# PS004.net
KiCad netlist of a schematic drawn in Altium Designer
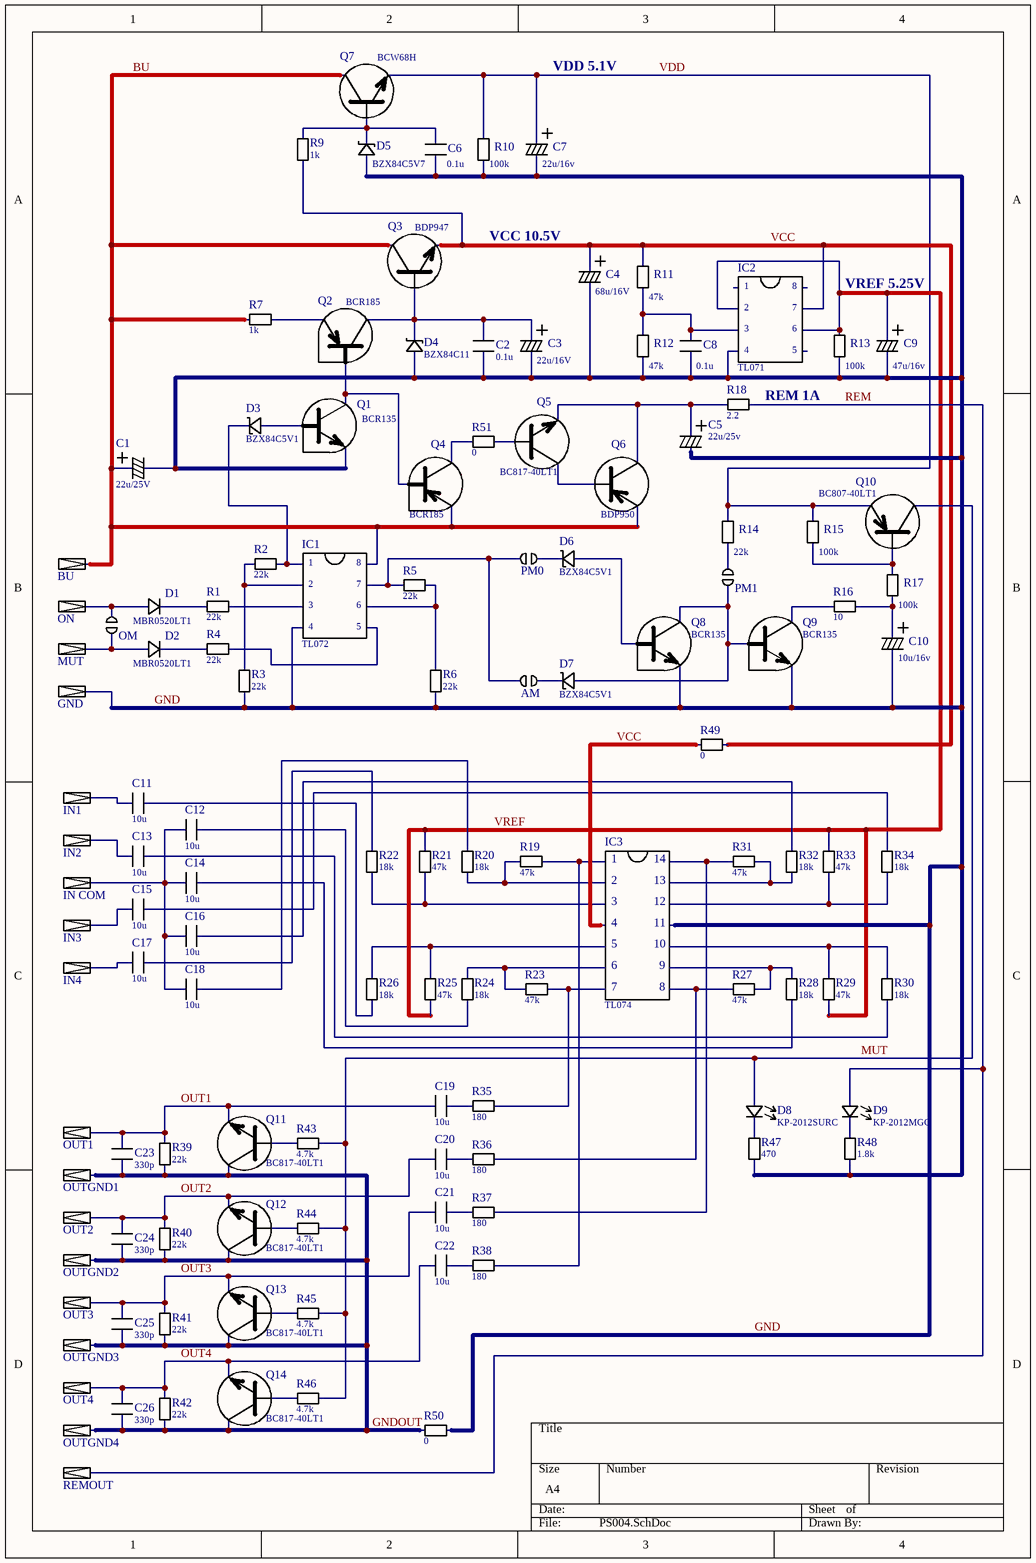
[diagram p0: PS004.SchDoc]

(export (version "E")
  (design (tool "Eeschema 10.0.6"))
  (components
    (comp (ref "AM") (value "SC plan") (footprint "SC") (libsource (lib "PS004") (part "SC plan")))
    (comp (ref "BU") (value "IN plan") (footprint "IO") (libsource (lib "PS004") (part "IN plan")))
    (comp (ref "C1")
      (value "C plan pol")
      (footprint "C")
      (fields (field (name "CAPASITANCE") "22u/25V"))
      (libsource (lib "PS004") (part "C plan pol"))
    )
    (comp (ref "C2")
      (value "C plan cer")
      (footprint "0805")
      (fields (field (name "CAPASITANCE") "0.1u"))
      (libsource (lib "PS004") (part "C plan cer"))
    )
    (comp (ref "C3")
      (value "C plan pol")
      (footprint "C")
      (fields (field (name "CAPASITANCE") "22u/16V"))
      (libsource (lib "PS004") (part "C plan pol"))
    )
    (comp (ref "C4")
      (value "C plan pol")
      (footprint "C")
      (fields (field (name "CAPASITANCE") "68u/16V"))
      (libsource (lib "PS004") (part "C plan pol"))
    )
    (comp (ref "C5")
      (value "C plan pol")
      (footprint "C")
      (fields (field (name "CAPASITANCE") "22u/25v"))
      (libsource (lib "PS004") (part "C plan pol"))
    )
    (comp (ref "C6")
      (value "C plan cer")
      (footprint "0805")
      (fields (field (name "CAPASITANCE") "0.1u"))
      (libsource (lib "PS004") (part "C plan cer"))
    )
    (comp (ref "C7")
      (value "C plan pol")
      (footprint "C")
      (fields (field (name "CAPASITANCE") "22u/16v"))
      (libsource (lib "PS004") (part "C plan pol"))
    )
    (comp (ref "C8")
      (value "C plan cer")
      (footprint "0805")
      (fields (field (name "CAPASITANCE") "0.1u"))
      (libsource (lib "PS004") (part "C plan cer"))
    )
    (comp (ref "C9")
      (value "C plan pol")
      (footprint "C")
      (fields (field (name "CAPASITANCE") "47u/16v"))
      (libsource (lib "PS004") (part "C plan pol"))
    )
    (comp (ref "C10")
      (value "C plan pol")
      (footprint "C")
      (fields (field (name "CAPASITANCE") "10u/16v"))
      (libsource (lib "PS004") (part "C plan pol"))
    )
    (comp (ref "C11")
      (value "C plan cer")
      (footprint "1206")
      (fields (field (name "CAPASITANCE") "10u"))
      (libsource (lib "PS004") (part "C plan cer"))
    )
    (comp (ref "C12")
      (value "C plan cer")
      (footprint "1206")
      (fields (field (name "CAPASITANCE") "10u"))
      (libsource (lib "PS004") (part "C plan cer"))
    )
    (comp (ref "C13")
      (value "C plan cer")
      (footprint "1206")
      (fields (field (name "CAPASITANCE") "10u"))
      (libsource (lib "PS004") (part "C plan cer"))
    )
    (comp (ref "C14")
      (value "C plan cer")
      (footprint "1206")
      (fields (field (name "CAPASITANCE") "10u"))
      (libsource (lib "PS004") (part "C plan cer"))
    )
    (comp (ref "C15")
      (value "C plan cer")
      (footprint "1206")
      (fields (field (name "CAPASITANCE") "10u"))
      (libsource (lib "PS004") (part "C plan cer"))
    )
    (comp (ref "C16")
      (value "C plan cer")
      (footprint "1206")
      (fields (field (name "CAPASITANCE") "10u"))
      (libsource (lib "PS004") (part "C plan cer"))
    )
    (comp (ref "C17")
      (value "C plan cer")
      (footprint "1206")
      (fields (field (name "CAPASITANCE") "10u"))
      (libsource (lib "PS004") (part "C plan cer"))
    )
    (comp (ref "C18")
      (value "C plan cer")
      (footprint "1206")
      (fields (field (name "CAPASITANCE") "10u"))
      (libsource (lib "PS004") (part "C plan cer"))
    )
    (comp (ref "C19")
      (value "C plan cer")
      (footprint "1206")
      (fields (field (name "CAPASITANCE") "10u"))
      (libsource (lib "PS004") (part "C plan cer"))
    )
    (comp (ref "C20")
      (value "C plan cer")
      (footprint "1206")
      (fields (field (name "CAPASITANCE") "10u"))
      (libsource (lib "PS004") (part "C plan cer"))
    )
    (comp (ref "C21")
      (value "C plan cer")
      (footprint "1206")
      (fields (field (name "CAPASITANCE") "10u"))
      (libsource (lib "PS004") (part "C plan cer"))
    )
    (comp (ref "C22")
      (value "C plan cer")
      (footprint "1206")
      (fields (field (name "CAPASITANCE") "10u"))
      (libsource (lib "PS004") (part "C plan cer"))
    )
    (comp (ref "C23")
      (value "C plan cer")
      (footprint "0805")
      (fields (field (name "CAPASITANCE") "330p"))
      (libsource (lib "PS004") (part "C plan cer"))
    )
    (comp (ref "C24")
      (value "C plan cer")
      (footprint "0805")
      (fields (field (name "CAPASITANCE") "330p"))
      (libsource (lib "PS004") (part "C plan cer"))
    )
    (comp (ref "C25")
      (value "C plan cer")
      (footprint "0805")
      (fields (field (name "CAPASITANCE") "330p"))
      (libsource (lib "PS004") (part "C plan cer"))
    )
    (comp (ref "C26")
      (value "C plan cer")
      (footprint "0805")
      (fields (field (name "CAPASITANCE") "330p"))
      (libsource (lib "PS004") (part "C plan cer"))
    )
    (comp (ref "D1")
      (value "D plan")
      (footprint "SOD-123")
      (fields (field (name "NAME") "MBR0520LT1"))
      (libsource (lib "PS004") (part "D plan"))
    )
    (comp (ref "D2")
      (value "D plan")
      (footprint "SOD-123")
      (fields (field (name "NAME") "MBR0520LT1"))
      (libsource (lib "PS004") (part "D plan"))
    )
    (comp (ref "D3")
      (value "DZ plan")
      (footprint "SOT-23")
      (fields (field (name "NAME") "BZX84C5V1"))
      (libsource (lib "PS004") (part "DZ plan"))
    )
    (comp (ref "D4")
      (value "DZ plan")
      (footprint "SOT-23")
      (fields (field (name "NAME") "BZX84C11"))
      (libsource (lib "PS004") (part "DZ plan"))
    )
    (comp (ref "D5")
      (value "DZ plan")
      (footprint "SOT-23")
      (fields (field (name "NAME") "BZX84C5V7"))
      (libsource (lib "PS004") (part "DZ plan"))
    )
    (comp (ref "D6")
      (value "DZ plan")
      (footprint "SOT-23")
      (fields (field (name "NAME") "BZX84C5V1"))
      (libsource (lib "PS004") (part "DZ plan"))
    )
    (comp (ref "D7")
      (value "DZ plan")
      (footprint "SOT-23")
      (fields (field (name "NAME") "BZX84C5V1"))
      (libsource (lib "PS004") (part "DZ plan"))
    )
    (comp (ref "D8")
      (value "DI plan")
      (footprint "0805 DI")
      (fields (field (name "NAME") "KP-2012SURC"))
      (libsource (lib "PS004") (part "DI plan"))
    )
    (comp (ref "D9")
      (value "DI plan")
      (footprint "0805 DI")
      (fields (field (name "NAME") "KP-2012MGC"))
      (libsource (lib "PS004") (part "DI plan"))
    )
    (comp (ref "GND") (value "IN plan") (footprint "IO") (libsource (lib "PS004") (part "IN plan")))
    (comp (ref "IC1")
      (value "IC 8 plan")
      (footprint "SO-8")
      (fields (field (name "NAME") "TL072"))
      (libsource (lib "PS004") (part "IC 8 plan"))
    )
    (comp (ref "IC2")
      (value "IC 8 plan")
      (footprint "SO-8")
      (fields (field (name "NAME") "TL071"))
      (libsource (lib "PS004") (part "IC 8 plan"))
    )
    (comp (ref "IC3")
      (value "IC 14 plan")
      (footprint "SO-14")
      (fields (field (name "NAME") "TL074"))
      (libsource (lib "PS004") (part "IC 14 plan"))
    )
    (comp (ref "IN COM") (value "IN plan") (footprint "IO") (libsource (lib "PS004") (part "IN plan")))
    (comp (ref "IN1") (value "IN plan") (footprint "IO") (libsource (lib "PS004") (part "IN plan")))
    (comp (ref "IN2") (value "IN plan") (footprint "IO") (libsource (lib "PS004") (part "IN plan")))
    (comp (ref "IN3") (value "IN plan") (footprint "IO") (libsource (lib "PS004") (part "IN plan")))
    (comp (ref "IN4") (value "IN plan") (footprint "IO") (libsource (lib "PS004") (part "IN plan")))
    (comp (ref "MUT") (value "IN plan") (footprint "IO") (libsource (lib "PS004") (part "IN plan")))
    (comp (ref "OM") (value "SC plan") (footprint "SC") (libsource (lib "") (part "SC plan_1")))
    (comp (ref "ON") (value "IN plan") (footprint "IO") (libsource (lib "PS004") (part "IN plan")))
    (comp (ref "OUT1") (value "OUT plan") (footprint "IO") (libsource (lib "PS004") (part "OUT plan")))
    (comp (ref "OUT2") (value "OUT plan") (footprint "IO") (libsource (lib "PS004") (part "OUT plan")))
    (comp (ref "OUT3") (value "OUT plan") (footprint "IO") (libsource (lib "PS004") (part "OUT plan")))
    (comp (ref "OUT4") (value "OUT plan") (footprint "IO") (libsource (lib "PS004") (part "OUT plan")))
    (comp (ref "OUTGND1") (value "OUT plan") (footprint "IO") (libsource (lib "PS004") (part "OUT plan")))
    (comp (ref "OUTGND2") (value "OUT plan") (footprint "IO") (libsource (lib "PS004") (part "OUT plan")))
    (comp (ref "OUTGND3") (value "OUT plan") (footprint "IO") (libsource (lib "PS004") (part "OUT plan")))
    (comp (ref "OUTGND4") (value "OUT plan") (footprint "IO") (libsource (lib "PS004") (part "OUT plan")))
    (comp (ref "PM0") (value "SC plan") (footprint "SC") (libsource (lib "PS004") (part "SC plan")))
    (comp (ref "PM1") (value "SC plan") (footprint "SC") (libsource (lib "") (part "SC plan_1")))
    (comp (ref "Q1")
      (value "QD npn plan")
      (footprint "SOT-23")
      (fields (field (name "NAME") "BCR135"))
      (libsource (lib "PS004") (part "QD npn plan"))
    )
    (comp (ref "Q2")
      (value "QD pnp plan")
      (footprint "SOT-23")
      (fields (field (name "NAME") "BCR185"))
      (libsource (lib "PS004") (part "QD pnp plan"))
    )
    (comp (ref "Q3")
      (value "Q npn plan")
      (footprint "SOT-223")
      (fields (field (name "NAME") "BDP947"))
      (libsource (lib "") (part "Q npn plan_2"))
    )
    (comp (ref "Q4")
      (value "QD pnp plan")
      (footprint "SOT-23")
      (fields (field (name "NAME") "BCR185"))
      (libsource (lib "") (part "QD pnp plan_1"))
    )
    (comp (ref "Q5")
      (value "Q npn plan")
      (footprint "SOT-23")
      (fields (field (name "NAME") "BC817-40LT1"))
      (libsource (lib "") (part "Q npn plan_1"))
    )
    (comp (ref "Q6")
      (value "Q pnp plan")
      (footprint "SOT-223")
      (fields (field (name "NAME") "BDP950"))
      (libsource (lib "") (part "Q pnp plan_1"))
    )
    (comp (ref "Q7")
      (value "Q npn plan")
      (footprint "SOT-23")
      (fields (field (name "NAME") "BCW68H"))
      (libsource (lib "") (part "Q npn plan_2"))
    )
    (comp (ref "Q8")
      (value "QD npn plan")
      (footprint "SOT-23")
      (fields (field (name "NAME") "BCR135"))
      (libsource (lib "PS004") (part "QD npn plan"))
    )
    (comp (ref "Q9")
      (value "QD npn plan")
      (footprint "SOT-23")
      (fields (field (name "NAME") "BCR135"))
      (libsource (lib "PS004") (part "QD npn plan"))
    )
    (comp (ref "Q10")
      (value "Q pnp plan")
      (footprint "SOT-23")
      (fields (field (name "NAME") "BC807-40LT1"))
      (libsource (lib "PS004") (part "Q pnp plan"))
    )
    (comp (ref "Q11")
      (value "Q npn plan")
      (footprint "SOT-23")
      (fields (field (name "NAME") "BC817-40LT1"))
      (libsource (lib "PS004") (part "Q npn plan"))
    )
    (comp (ref "Q12")
      (value "Q npn plan")
      (footprint "SOT-23")
      (fields (field (name "NAME") "BC817-40LT1"))
      (libsource (lib "PS004") (part "Q npn plan"))
    )
    (comp (ref "Q13")
      (value "Q npn plan")
      (footprint "SOT-23")
      (fields (field (name "NAME") "BC817-40LT1"))
      (libsource (lib "PS004") (part "Q npn plan"))
    )
    (comp (ref "Q14")
      (value "Q npn plan")
      (footprint "SOT-23")
      (fields (field (name "NAME") "BC817-40LT1"))
      (libsource (lib "PS004") (part "Q npn plan"))
    )
    (comp (ref "R1")
      (value "R plan")
      (footprint "0805")
      (fields (field (name "RESISTANCE") "22k"))
      (libsource (lib "PS004") (part "R plan"))
    )
    (comp (ref "R2")
      (value "R plan")
      (footprint "0805")
      (fields (field (name "RESISTANCE") "22k"))
      (libsource (lib "PS004") (part "R plan"))
    )
    (comp (ref "R3")
      (value "R plan")
      (footprint "0805")
      (fields (field (name "RESISTANCE") "22k"))
      (libsource (lib "PS004") (part "R plan"))
    )
    (comp (ref "R4")
      (value "R plan")
      (footprint "0805")
      (fields (field (name "RESISTANCE") "22k"))
      (libsource (lib "PS004") (part "R plan"))
    )
    (comp (ref "R5")
      (value "R plan")
      (footprint "0805")
      (fields (field (name "RESISTANCE") "22k"))
      (libsource (lib "PS004") (part "R plan"))
    )
    (comp (ref "R6")
      (value "R plan")
      (footprint "0805")
      (fields (field (name "RESISTANCE") "22k"))
      (libsource (lib "PS004") (part "R plan"))
    )
    (comp (ref "R7")
      (value "R plan")
      (footprint "0805")
      (fields (field (name "RESISTANCE") "1k"))
      (libsource (lib "PS004") (part "R plan"))
    )
    (comp (ref "R9")
      (value "R plan")
      (footprint "0805")
      (fields (field (name "RESISTANCE") "1k"))
      (libsource (lib "PS004") (part "R plan"))
    )
    (comp (ref "R10")
      (value "R plan")
      (footprint "0805")
      (fields (field (name "RESISTANCE") "100k"))
      (libsource (lib "PS004") (part "R plan"))
    )
    (comp (ref "R11")
      (value "R plan")
      (footprint "0805")
      (fields (field (name "RESISTANCE") "47k"))
      (libsource (lib "PS004") (part "R plan"))
    )
    (comp (ref "R12")
      (value "R plan")
      (footprint "0805")
      (fields (field (name "RESISTANCE") "47k"))
      (libsource (lib "PS004") (part "R plan"))
    )
    (comp (ref "R13")
      (value "R plan")
      (footprint "0805")
      (fields (field (name "RESISTANCE") "100k"))
      (libsource (lib "PS004") (part "R plan"))
    )
    (comp (ref "R14")
      (value "R plan")
      (footprint "0805")
      (fields (field (name "RESISTANCE") "22k"))
      (libsource (lib "PS004") (part "R plan"))
    )
    (comp (ref "R15")
      (value "R plan")
      (footprint "0805")
      (fields (field (name "RESISTANCE") "100k"))
      (libsource (lib "PS004") (part "R plan"))
    )
    (comp (ref "R16")
      (value "R plan")
      (footprint "0805")
      (fields (field (name "RESISTANCE") "10"))
      (libsource (lib "PS004") (part "R plan"))
    )
    (comp (ref "R17")
      (value "R plan")
      (footprint "0805")
      (fields (field (name "RESISTANCE") "100k"))
      (libsource (lib "PS004") (part "R plan"))
    )
    (comp (ref "R18")
      (value "R plan")
      (footprint "1210")
      (fields (field (name "RESISTANCE") "2.2"))
      (libsource (lib "PS004") (part "R plan"))
    )
    (comp (ref "R19")
      (value "R plan")
      (footprint "0805")
      (fields (field (name "RESISTANCE") "47k"))
      (libsource (lib "PS004") (part "R plan"))
    )
    (comp (ref "R20")
      (value "R plan")
      (footprint "0805")
      (fields (field (name "RESISTANCE") "18k"))
      (libsource (lib "PS004") (part "R plan"))
    )
    (comp (ref "R21")
      (value "R plan")
      (footprint "0805")
      (fields (field (name "RESISTANCE") "47k"))
      (libsource (lib "PS004") (part "R plan"))
    )
    (comp (ref "R22")
      (value "R plan")
      (footprint "0805")
      (fields (field (name "RESISTANCE") "18k"))
      (libsource (lib "PS004") (part "R plan"))
    )
    (comp (ref "R23")
      (value "R plan")
      (footprint "0805")
      (fields (field (name "RESISTANCE") "47k"))
      (libsource (lib "PS004") (part "R plan"))
    )
    (comp (ref "R24")
      (value "R plan")
      (footprint "0805")
      (fields (field (name "RESISTANCE") "18k"))
      (libsource (lib "PS004") (part "R plan"))
    )
    (comp (ref "R25")
      (value "R plan")
      (footprint "0805")
      (fields (field (name "RESISTANCE") "47k"))
      (libsource (lib "PS004") (part "R plan"))
    )
    (comp (ref "R26")
      (value "R plan")
      (footprint "0805")
      (fields (field (name "RESISTANCE") "18k"))
      (libsource (lib "PS004") (part "R plan"))
    )
    (comp (ref "R27")
      (value "R plan")
      (footprint "0805")
      (fields (field (name "RESISTANCE") "47k"))
      (libsource (lib "PS004") (part "R plan"))
    )
    (comp (ref "R28")
      (value "R plan")
      (footprint "0805")
      (fields (field (name "RESISTANCE") "18k"))
      (libsource (lib "PS004") (part "R plan"))
    )
    (comp (ref "R29")
      (value "R plan")
      (footprint "0805")
      (fields (field (name "RESISTANCE") "47k"))
      (libsource (lib "PS004") (part "R plan"))
    )
    (comp (ref "R30")
      (value "R plan")
      (footprint "0805")
      (fields (field (name "RESISTANCE") "18k"))
      (libsource (lib "PS004") (part "R plan"))
    )
    (comp (ref "R31")
      (value "R plan")
      (footprint "0805")
      (fields (field (name "RESISTANCE") "47k"))
      (libsource (lib "PS004") (part "R plan"))
    )
    (comp (ref "R32")
      (value "R plan")
      (footprint "0805")
      (fields (field (name "RESISTANCE") "18k"))
      (libsource (lib "PS004") (part "R plan"))
    )
    (comp (ref "R33")
      (value "R plan")
      (footprint "0805")
      (fields (field (name "RESISTANCE") "47k"))
      (libsource (lib "PS004") (part "R plan"))
    )
    (comp (ref "R34")
      (value "R plan")
      (footprint "0805")
      (fields (field (name "RESISTANCE") "18k"))
      (libsource (lib "PS004") (part "R plan"))
    )
    (comp (ref "R35")
      (value "R plan")
      (footprint "0805")
      (fields (field (name "RESISTANCE") "180"))
      (libsource (lib "PS004") (part "R plan"))
    )
    (comp (ref "R36")
      (value "R plan")
      (footprint "0805")
      (fields (field (name "RESISTANCE") "180"))
      (libsource (lib "PS004") (part "R plan"))
    )
    (comp (ref "R37")
      (value "R plan")
      (footprint "0805")
      (fields (field (name "RESISTANCE") "180"))
      (libsource (lib "PS004") (part "R plan"))
    )
    (comp (ref "R38")
      (value "R plan")
      (footprint "0805")
      (fields (field (name "RESISTANCE") "180"))
      (libsource (lib "PS004") (part "R plan"))
    )
    (comp (ref "R39")
      (value "R plan")
      (footprint "0805")
      (fields (field (name "RESISTANCE") "22k"))
      (libsource (lib "PS004") (part "R plan"))
    )
    (comp (ref "R40")
      (value "R plan")
      (footprint "0805")
      (fields (field (name "RESISTANCE") "22k"))
      (libsource (lib "PS004") (part "R plan"))
    )
    (comp (ref "R41")
      (value "R plan")
      (footprint "0805")
      (fields (field (name "RESISTANCE") "22k"))
      (libsource (lib "PS004") (part "R plan"))
    )
    (comp (ref "R42")
      (value "R plan")
      (footprint "0805")
      (fields (field (name "RESISTANCE") "22k"))
      (libsource (lib "PS004") (part "R plan"))
    )
    (comp (ref "R43")
      (value "R plan")
      (footprint "0805")
      (fields (field (name "RESISTANCE") "4.7k"))
      (libsource (lib "PS004") (part "R plan"))
    )
    (comp (ref "R44")
      (value "R plan")
      (footprint "0805")
      (fields (field (name "RESISTANCE") "4.7k"))
      (libsource (lib "PS004") (part "R plan"))
    )
    (comp (ref "R45")
      (value "R plan")
      (footprint "0805")
      (fields (field (name "RESISTANCE") "4.7k"))
      (libsource (lib "PS004") (part "R plan"))
    )
    (comp (ref "R46")
      (value "R plan")
      (footprint "0805")
      (fields (field (name "RESISTANCE") "4.7k"))
      (libsource (lib "PS004") (part "R plan"))
    )
    (comp (ref "R47")
      (value "R plan")
      (footprint "0805")
      (fields (field (name "RESISTANCE") "470"))
      (libsource (lib "PS004") (part "R plan"))
    )
    (comp (ref "R48")
      (value "R plan")
      (footprint "0805")
      (fields (field (name "RESISTANCE") "1.8k"))
      (libsource (lib "PS004") (part "R plan"))
    )
    (comp (ref "R49")
      (value "R plan")
      (footprint "0805")
      (fields (field (name "RESISTANCE") "0"))
      (libsource (lib "PS004") (part "R plan"))
    )
    (comp (ref "R50")
      (value "R plan")
      (footprint "0805")
      (fields (field (name "RESISTANCE") "0"))
      (libsource (lib "PS004") (part "R plan"))
    )
    (comp (ref "R51")
      (value "R plan")
      (footprint "0805")
      (fields (field (name "RESISTANCE") "0"))
      (libsource (lib "PS004") (part "R plan"))
    )
    (comp (ref "REMOUT") (value "OUT plan") (footprint "IOEX") (libsource (lib "PS004") (part "OUT plan")))
  )
  (nets
    (net (code "1") (name "/BU") (class "Default")
      (node (ref "BU") (pin "1") (pinfunction "1_1") (pintype "passive"))
      (node (ref "C1") (pin "1") (pinfunction "1_1") (pintype "passive"))
      (node (ref "IC1") (pin "8") (pinfunction "8_8") (pintype "passive"))
      (node (ref "Q3") (pin "2") (pinfunction "2_2") (pintype "passive"))
      (node (ref "Q4") (pin "3") (pinfunction "3_3") (pintype "passive"))
      (node (ref "Q6") (pin "3") (pinfunction "3_3") (pintype "passive"))
      (node (ref "Q7") (pin "2") (pinfunction "2_2") (pintype "passive"))
      (node (ref "R7") (pin "1") (pinfunction "1_1") (pintype "passive"))
    )
    (net (code "2") (name "/GND") (class "Default")
      (node (ref "C1") (pin "2") (pinfunction "2_2") (pintype "passive"))
      (node (ref "C10") (pin "2") (pinfunction "2_2") (pintype "passive"))
      (node (ref "C2") (pin "1") (pinfunction "1_1") (pintype "passive"))
      (node (ref "C3") (pin "2") (pinfunction "2_2") (pintype "passive"))
      (node (ref "C4") (pin "2") (pinfunction "2_2") (pintype "passive"))
      (node (ref "C5") (pin "2") (pinfunction "2_2") (pintype "passive"))
      (node (ref "C6") (pin "1") (pinfunction "1_1") (pintype "passive"))
      (node (ref "C7") (pin "2") (pinfunction "2_2") (pintype "passive"))
      (node (ref "C8") (pin "1") (pinfunction "1_1") (pintype "passive"))
      (node (ref "C9") (pin "2") (pinfunction "2_2") (pintype "passive"))
      (node (ref "D4") (pin "1") (pinfunction "1_1") (pintype "passive"))
      (node (ref "D5") (pin "1") (pinfunction "1_1") (pintype "passive"))
      (node (ref "GND") (pin "1") (pinfunction "1_1") (pintype "passive"))
      (node (ref "IC1") (pin "4") (pinfunction "4_4") (pintype "passive"))
      (node (ref "IC2") (pin "4") (pinfunction "4_4") (pintype "passive"))
      (node (ref "IC3") (pin "11") (pinfunction "11_11") (pintype "passive"))
      (node (ref "Q1") (pin "3") (pinfunction "3_3") (pintype "passive"))
      (node (ref "Q8") (pin "3") (pinfunction "3_3") (pintype "passive"))
      (node (ref "Q9") (pin "3") (pinfunction "3_3") (pintype "passive"))
      (node (ref "R10") (pin "1") (pinfunction "1_1") (pintype "passive"))
      (node (ref "R12") (pin "1") (pinfunction "1_1") (pintype "passive"))
      (node (ref "R13") (pin "1") (pinfunction "1_1") (pintype "passive"))
      (node (ref "R3") (pin "1") (pinfunction "1_1") (pintype "passive"))
      (node (ref "R47") (pin "1") (pinfunction "1_1") (pintype "passive"))
      (node (ref "R48") (pin "1") (pinfunction "1_1") (pintype "passive"))
      (node (ref "R50") (pin "2") (pinfunction "2_2") (pintype "passive"))
      (node (ref "R6") (pin "1") (pinfunction "1_1") (pintype "passive"))
    )
    (net (code "3") (name "/GNDOUT") (class "Default")
      (node (ref "C23") (pin "1") (pinfunction "1_1") (pintype "passive"))
      (node (ref "C24") (pin "1") (pinfunction "1_1") (pintype "passive"))
      (node (ref "C25") (pin "1") (pinfunction "1_1") (pintype "passive"))
      (node (ref "C26") (pin "1") (pinfunction "1_1") (pintype "passive"))
      (node (ref "OUTGND1") (pin "1") (pinfunction "1_1") (pintype "passive"))
      (node (ref "OUTGND2") (pin "1") (pinfunction "1_1") (pintype "passive"))
      (node (ref "OUTGND3") (pin "1") (pinfunction "1_1") (pintype "passive"))
      (node (ref "OUTGND4") (pin "1") (pinfunction "1_1") (pintype "passive"))
      (node (ref "Q11") (pin "2") (pinfunction "2_2") (pintype "passive"))
      (node (ref "Q12") (pin "2") (pinfunction "2_2") (pintype "passive"))
      (node (ref "Q13") (pin "2") (pinfunction "2_2") (pintype "passive"))
      (node (ref "Q14") (pin "2") (pinfunction "2_2") (pintype "passive"))
      (node (ref "R39") (pin "1") (pinfunction "1_1") (pintype "passive"))
      (node (ref "R40") (pin "1") (pinfunction "1_1") (pintype "passive"))
      (node (ref "R41") (pin "1") (pinfunction "1_1") (pintype "passive"))
      (node (ref "R42") (pin "1") (pinfunction "1_1") (pintype "passive"))
      (node (ref "R50") (pin "1") (pinfunction "1_1") (pintype "passive"))
    )
    (net (code "4") (name "/MUT") (class "Default")
      (node (ref "D8") (pin "2") (pinfunction "2_2") (pintype "passive"))
      (node (ref "Q10") (pin "2") (pinfunction "2_2") (pintype "passive"))
      (node (ref "R43") (pin "2") (pinfunction "2_2") (pintype "passive"))
      (node (ref "R44") (pin "2") (pinfunction "2_2") (pintype "passive"))
      (node (ref "R45") (pin "2") (pinfunction "2_2") (pintype "passive"))
      (node (ref "R46") (pin "2") (pinfunction "2_2") (pintype "passive"))
    )
    (net (code "5") (name "/OUT1") (class "Default")
      (node (ref "C19") (pin "1") (pinfunction "1_1") (pintype "passive"))
      (node (ref "C23") (pin "2") (pinfunction "2_2") (pintype "passive"))
      (node (ref "OUT1") (pin "1") (pinfunction "1_1") (pintype "passive"))
      (node (ref "Q11") (pin "3") (pinfunction "3_3") (pintype "passive"))
      (node (ref "R39") (pin "2") (pinfunction "2_2") (pintype "passive"))
    )
    (net (code "6") (name "/OUT2") (class "Default")
      (node (ref "C20") (pin "1") (pinfunction "1_1") (pintype "passive"))
      (node (ref "C24") (pin "2") (pinfunction "2_2") (pintype "passive"))
      (node (ref "OUT2") (pin "1") (pinfunction "1_1") (pintype "passive"))
      (node (ref "Q12") (pin "3") (pinfunction "3_3") (pintype "passive"))
      (node (ref "R40") (pin "2") (pinfunction "2_2") (pintype "passive"))
    )
    (net (code "7") (name "/OUT3") (class "Default")
      (node (ref "C21") (pin "1") (pinfunction "1_1") (pintype "passive"))
      (node (ref "C25") (pin "2") (pinfunction "2_2") (pintype "passive"))
      (node (ref "OUT3") (pin "1") (pinfunction "1_1") (pintype "passive"))
      (node (ref "Q13") (pin "3") (pinfunction "3_3") (pintype "passive"))
      (node (ref "R41") (pin "2") (pinfunction "2_2") (pintype "passive"))
    )
    (net (code "8") (name "/OUT4") (class "Default")
      (node (ref "C22") (pin "1") (pinfunction "1_1") (pintype "passive"))
      (node (ref "C26") (pin "2") (pinfunction "2_2") (pintype "passive"))
      (node (ref "OUT4") (pin "1") (pinfunction "1_1") (pintype "passive"))
      (node (ref "Q14") (pin "3") (pinfunction "3_3") (pintype "passive"))
      (node (ref "R42") (pin "2") (pinfunction "2_2") (pintype "passive"))
    )
    (net (code "9") (name "/REM") (class "Default")
      (node (ref "D9") (pin "2") (pinfunction "2_2") (pintype "passive"))
      (node (ref "R18") (pin "2") (pinfunction "2_2") (pintype "passive"))
      (node (ref "REMOUT") (pin "1") (pinfunction "1_1") (pintype "passive"))
    )
    (net (code "10") (name "/VCC") (class "Default")
      (node (ref "C4") (pin "1") (pinfunction "1_1") (pintype "passive"))
      (node (ref "IC2") (pin "7") (pinfunction "7_7") (pintype "passive"))
      (node (ref "IC3") (pin "4") (pinfunction "4_4") (pintype "passive"))
      (node (ref "Q3") (pin "3") (pinfunction "3_3") (pintype "passive"))
      (node (ref "R11") (pin "2") (pinfunction "2_2") (pintype "passive"))
      (node (ref "R49") (pin "1") (pinfunction "1_1") (pintype "passive"))
      (node (ref "R49") (pin "2") (pinfunction "2_2") (pintype "passive"))
      (node (ref "R9") (pin "1") (pinfunction "1_1") (pintype "passive"))
    )
    (net (code "11") (name "/VDD") (class "Default")
      (node (ref "C7") (pin "1") (pinfunction "1_1") (pintype "passive"))
      (node (ref "Q10") (pin "3") (pinfunction "3_3") (pintype "passive"))
      (node (ref "Q7") (pin "3") (pinfunction "3_3") (pintype "passive"))
      (node (ref "R10") (pin "2") (pinfunction "2_2") (pintype "passive"))
      (node (ref "R14") (pin "2") (pinfunction "2_2") (pintype "passive"))
      (node (ref "R15") (pin "2") (pinfunction "2_2") (pintype "passive"))
    )
    (net (code "12") (name "/VREF") (class "Default")
      (node (ref "C9") (pin "1") (pinfunction "1_1") (pintype "passive"))
      (node (ref "IC2") (pin "2") (pinfunction "2_2") (pintype "passive"))
      (node (ref "IC2") (pin "6") (pinfunction "6_6") (pintype "passive"))
      (node (ref "R13") (pin "2") (pinfunction "2_2") (pintype "passive"))
      (node (ref "R21") (pin "2") (pinfunction "2_2") (pintype "passive"))
      (node (ref "R25") (pin "2") (pinfunction "2_2") (pintype "passive"))
      (node (ref "R29") (pin "1") (pinfunction "1_1") (pintype "passive"))
      (node (ref "R33") (pin "1") (pinfunction "1_1") (pintype "passive"))
    )
    (net (code "13") (name "Net-(AM-Pad1)") (class "Default")
      (node (ref "AM") (pin "1") (pinfunction "1_1") (pintype "passive"))
      (node (ref "IC1") (pin "7") (pinfunction "7_7") (pintype "passive"))
      (node (ref "PM0") (pin "1") (pinfunction "1_1") (pintype "passive"))
      (node (ref "R5") (pin "1") (pinfunction "1_1") (pintype "passive"))
    )
    (net (code "14") (name "Net-(AM-Pad2)") (class "Default")
      (node (ref "AM") (pin "2") (pinfunction "2_2") (pintype "passive"))
      (node (ref "D7") (pin "2") (pinfunction "2_2") (pintype "passive"))
    )
    (net (code "15") (name "Net-(C2-Pad2)") (class "Default")
      (node (ref "C2") (pin "2") (pinfunction "2_2") (pintype "passive"))
      (node (ref "C3") (pin "1") (pinfunction "1_1") (pintype "passive"))
      (node (ref "D4") (pin "2") (pinfunction "2_2") (pintype "passive"))
      (node (ref "Q2") (pin "2") (pinfunction "2_2") (pintype "passive"))
      (node (ref "Q3") (pin "1") (pinfunction "1_1") (pintype "passive"))
    )
    (net (code "16") (name "Net-(C5-Pad1)") (class "Default")
      (node (ref "C5") (pin "1") (pinfunction "1_1") (pintype "passive"))
      (node (ref "Q5") (pin "3") (pinfunction "3_3") (pintype "passive"))
      (node (ref "Q6") (pin "2") (pinfunction "2_2") (pintype "passive"))
      (node (ref "R18") (pin "1") (pinfunction "1_1") (pintype "passive"))
    )
    (net (code "17") (name "Net-(C6-Pad2)") (class "Default")
      (node (ref "C6") (pin "2") (pinfunction "2_2") (pintype "passive"))
      (node (ref "D5") (pin "2") (pinfunction "2_2") (pintype "passive"))
      (node (ref "Q7") (pin "1") (pinfunction "1_1") (pintype "passive"))
      (node (ref "R9") (pin "2") (pinfunction "2_2") (pintype "passive"))
    )
    (net (code "18") (name "Net-(C8-Pad2)") (class "Default")
      (node (ref "C8") (pin "2") (pinfunction "2_2") (pintype "passive"))
      (node (ref "IC2") (pin "3") (pinfunction "3_3") (pintype "passive"))
      (node (ref "R11") (pin "1") (pinfunction "1_1") (pintype "passive"))
      (node (ref "R12") (pin "2") (pinfunction "2_2") (pintype "passive"))
    )
    (net (code "19") (name "Net-(C10-Pad1)") (class "Default")
      (node (ref "C10") (pin "1") (pinfunction "1_1") (pintype "passive"))
      (node (ref "R16") (pin "1") (pinfunction "1_1") (pintype "passive"))
      (node (ref "R17") (pin "1") (pinfunction "1_1") (pintype "passive"))
    )
    (net (code "20") (name "Net-(C11-Pad1)") (class "Default")
      (node (ref "C11") (pin "1") (pinfunction "1_1") (pintype "passive"))
      (node (ref "IN1") (pin "1") (pinfunction "1_1") (pintype "passive"))
    )
    (net (code "21") (name "Net-(C11-Pad2)") (class "Default")
      (node (ref "C11") (pin "2") (pinfunction "2_2") (pintype "passive"))
      (node (ref "R26") (pin "2") (pinfunction "2_2") (pintype "passive"))
    )
    (net (code "22") (name "Net-(C12-Pad1)") (class "Default")
      (node (ref "C12") (pin "1") (pinfunction "1_1") (pintype "passive"))
      (node (ref "C14") (pin "1") (pinfunction "1_1") (pintype "passive"))
      (node (ref "C16") (pin "1") (pinfunction "1_1") (pintype "passive"))
      (node (ref "C18") (pin "1") (pinfunction "1_1") (pintype "passive"))
      (node (ref "IN COM") (pin "1") (pinfunction "1_1") (pintype "passive"))
    )
    (net (code "23") (name "Net-(C12-Pad2)") (class "Default")
      (node (ref "C12") (pin "2") (pinfunction "2_2") (pintype "passive"))
      (node (ref "R24") (pin "2") (pinfunction "2_2") (pintype "passive"))
    )
    (net (code "24") (name "Net-(C13-Pad1)") (class "Default")
      (node (ref "C13") (pin "1") (pinfunction "1_1") (pintype "passive"))
      (node (ref "IN2") (pin "1") (pinfunction "1_1") (pintype "passive"))
    )
    (net (code "25") (name "Net-(C13-Pad2)") (class "Default")
      (node (ref "C13") (pin "2") (pinfunction "2_2") (pintype "passive"))
      (node (ref "R30") (pin "1") (pinfunction "1_1") (pintype "passive"))
    )
    (net (code "26") (name "Net-(C14-Pad2)") (class "Default")
      (node (ref "C14") (pin "2") (pinfunction "2_2") (pintype "passive"))
      (node (ref "R28") (pin "1") (pinfunction "1_1") (pintype "passive"))
    )
    (net (code "27") (name "Net-(C15-Pad1)") (class "Default")
      (node (ref "C15") (pin "1") (pinfunction "1_1") (pintype "passive"))
      (node (ref "IN3") (pin "1") (pinfunction "1_1") (pintype "passive"))
    )
    (net (code "28") (name "Net-(C15-Pad2)") (class "Default")
      (node (ref "C15") (pin "2") (pinfunction "2_2") (pintype "passive"))
      (node (ref "R34") (pin "1") (pinfunction "1_1") (pintype "passive"))
    )
    (net (code "29") (name "Net-(C16-Pad2)") (class "Default")
      (node (ref "C16") (pin "2") (pinfunction "2_2") (pintype "passive"))
      (node (ref "R32") (pin "1") (pinfunction "1_1") (pintype "passive"))
    )
    (net (code "30") (name "Net-(C17-Pad1)") (class "Default")
      (node (ref "C17") (pin "1") (pinfunction "1_1") (pintype "passive"))
      (node (ref "IN4") (pin "1") (pinfunction "1_1") (pintype "passive"))
    )
    (net (code "31") (name "Net-(C17-Pad2)") (class "Default")
      (node (ref "C17") (pin "2") (pinfunction "2_2") (pintype "passive"))
      (node (ref "R22") (pin "2") (pinfunction "2_2") (pintype "passive"))
    )
    (net (code "32") (name "Net-(C18-Pad2)") (class "Default")
      (node (ref "C18") (pin "2") (pinfunction "2_2") (pintype "passive"))
      (node (ref "R20") (pin "2") (pinfunction "2_2") (pintype "passive"))
    )
    (net (code "33") (name "Net-(C19-Pad2)") (class "Default")
      (node (ref "C19") (pin "2") (pinfunction "2_2") (pintype "passive"))
      (node (ref "R35") (pin "1") (pinfunction "1_1") (pintype "passive"))
    )
    (net (code "34") (name "Net-(C20-Pad2)") (class "Default")
      (node (ref "C20") (pin "2") (pinfunction "2_2") (pintype "passive"))
      (node (ref "R36") (pin "1") (pinfunction "1_1") (pintype "passive"))
    )
    (net (code "35") (name "Net-(C21-Pad2)") (class "Default")
      (node (ref "C21") (pin "2") (pinfunction "2_2") (pintype "passive"))
      (node (ref "R37") (pin "1") (pinfunction "1_1") (pintype "passive"))
    )
    (net (code "36") (name "Net-(C22-Pad2)") (class "Default")
      (node (ref "C22") (pin "2") (pinfunction "2_2") (pintype "passive"))
      (node (ref "R38") (pin "1") (pinfunction "1_1") (pintype "passive"))
    )
    (net (code "37") (name "Net-(D1-Pad1)") (class "Default")
      (node (ref "D1") (pin "1") (pinfunction "1_1") (pintype "passive"))
      (node (ref "R1") (pin "1") (pinfunction "1_1") (pintype "passive"))
    )
    (net (code "38") (name "Net-(D1-Pad2)") (class "Default")
      (node (ref "D1") (pin "2") (pinfunction "2_2") (pintype "passive"))
      (node (ref "OM") (pin "2") (pinfunction "2_2") (pintype "passive"))
      (node (ref "ON") (pin "1") (pinfunction "1_1") (pintype "passive"))
    )
    (net (code "39") (name "Net-(D2-Pad1)") (class "Default")
      (node (ref "D2") (pin "1") (pinfunction "1_1") (pintype "passive"))
      (node (ref "R4") (pin "1") (pinfunction "1_1") (pintype "passive"))
    )
    (net (code "40") (name "Net-(D2-Pad2)") (class "Default")
      (node (ref "D2") (pin "2") (pinfunction "2_2") (pintype "passive"))
      (node (ref "MUT") (pin "1") (pinfunction "1_1") (pintype "passive"))
      (node (ref "OM") (pin "1") (pinfunction "1_1") (pintype "passive"))
    )
    (net (code "41") (name "Net-(D3-Pad1)") (class "Default")
      (node (ref "D3") (pin "1") (pinfunction "1_1") (pintype "passive"))
      (node (ref "Q1") (pin "1") (pinfunction "1_1") (pintype "passive"))
    )
    (net (code "42") (name "Net-(D3-Pad2)") (class "Default")
      (node (ref "D3") (pin "2") (pinfunction "2_2") (pintype "passive"))
      (node (ref "IC1") (pin "1") (pinfunction "1_1") (pintype "passive"))
      (node (ref "R2") (pin "2") (pinfunction "2_2") (pintype "passive"))
    )
    (net (code "43") (name "Net-(D6-Pad1)") (class "Default")
      (node (ref "D6") (pin "1") (pinfunction "1_1") (pintype "passive"))
      (node (ref "Q8") (pin "1") (pinfunction "1_1") (pintype "passive"))
    )
    (net (code "44") (name "Net-(D6-Pad2)") (class "Default")
      (node (ref "D6") (pin "2") (pinfunction "2_2") (pintype "passive"))
      (node (ref "PM0") (pin "2") (pinfunction "2_2") (pintype "passive"))
    )
    (net (code "45") (name "Net-(D7-Pad1)") (class "Default")
      (node (ref "D7") (pin "1") (pinfunction "1_1") (pintype "passive"))
      (node (ref "PM1") (pin "1") (pinfunction "1_1") (pintype "passive"))
      (node (ref "Q8") (pin "2") (pinfunction "2_2") (pintype "passive"))
      (node (ref "Q9") (pin "1") (pinfunction "1_1") (pintype "passive"))
    )
    (net (code "46") (name "Net-(D8-Pad1)") (class "Default")
      (node (ref "D8") (pin "1") (pinfunction "1_1") (pintype "passive"))
      (node (ref "R47") (pin "2") (pinfunction "2_2") (pintype "passive"))
    )
    (net (code "47") (name "Net-(D9-Pad1)") (class "Default")
      (node (ref "D9") (pin "1") (pinfunction "1_1") (pintype "passive"))
      (node (ref "R48") (pin "2") (pinfunction "2_2") (pintype "passive"))
    )
    (net (code "48") (name "Net-(IC1-Pad2)") (class "Default")
      (node (ref "IC1") (pin "2") (pinfunction "2_2") (pintype "passive"))
      (node (ref "R2") (pin "1") (pinfunction "1_1") (pintype "passive"))
      (node (ref "R3") (pin "2") (pinfunction "2_2") (pintype "passive"))
    )
    (net (code "49") (name "Net-(IC1-Pad3)") (class "Default")
      (node (ref "IC1") (pin "3") (pinfunction "3_3") (pintype "passive"))
      (node (ref "R1") (pin "2") (pinfunction "2_2") (pintype "passive"))
    )
    (net (code "50") (name "Net-(IC1-Pad5)") (class "Default")
      (node (ref "IC1") (pin "5") (pinfunction "5_5") (pintype "passive"))
      (node (ref "R4") (pin "2") (pinfunction "2_2") (pintype "passive"))
    )
    (net (code "51") (name "Net-(IC1-Pad6)") (class "Default")
      (node (ref "IC1") (pin "6") (pinfunction "6_6") (pintype "passive"))
      (node (ref "R5") (pin "2") (pinfunction "2_2") (pintype "passive"))
      (node (ref "R6") (pin "2") (pinfunction "2_2") (pintype "passive"))
    )
    (net (code "52") (name "Net-(IC3-Pad1)") (class "Default")
      (node (ref "IC3") (pin "1") (pinfunction "1_1") (pintype "passive"))
      (node (ref "R19") (pin "2") (pinfunction "2_2") (pintype "passive"))
      (node (ref "R38") (pin "2") (pinfunction "2_2") (pintype "passive"))
    )
    (net (code "53") (name "Net-(IC3-Pad2)") (class "Default")
      (node (ref "IC3") (pin "2") (pinfunction "2_2") (pintype "passive"))
      (node (ref "R19") (pin "1") (pinfunction "1_1") (pintype "passive"))
      (node (ref "R20") (pin "1") (pinfunction "1_1") (pintype "passive"))
    )
    (net (code "54") (name "Net-(IC3-Pad3)") (class "Default")
      (node (ref "IC3") (pin "3") (pinfunction "3_3") (pintype "passive"))
      (node (ref "R21") (pin "1") (pinfunction "1_1") (pintype "passive"))
      (node (ref "R22") (pin "1") (pinfunction "1_1") (pintype "passive"))
    )
    (net (code "55") (name "Net-(IC3-Pad5)") (class "Default")
      (node (ref "IC3") (pin "5") (pinfunction "5_5") (pintype "passive"))
      (node (ref "R25") (pin "1") (pinfunction "1_1") (pintype "passive"))
      (node (ref "R26") (pin "1") (pinfunction "1_1") (pintype "passive"))
    )
    (net (code "56") (name "Net-(IC3-Pad6)") (class "Default")
      (node (ref "IC3") (pin "6") (pinfunction "6_6") (pintype "passive"))
      (node (ref "R23") (pin "2") (pinfunction "2_2") (pintype "passive"))
      (node (ref "R24") (pin "1") (pinfunction "1_1") (pintype "passive"))
    )
    (net (code "57") (name "Net-(IC3-Pad7)") (class "Default")
      (node (ref "IC3") (pin "7") (pinfunction "7_7") (pintype "passive"))
      (node (ref "R23") (pin "1") (pinfunction "1_1") (pintype "passive"))
      (node (ref "R35") (pin "2") (pinfunction "2_2") (pintype "passive"))
    )
    (net (code "58") (name "Net-(IC3-Pad8)") (class "Default")
      (node (ref "IC3") (pin "8") (pinfunction "8_8") (pintype "passive"))
      (node (ref "R27") (pin "1") (pinfunction "1_1") (pintype "passive"))
      (node (ref "R36") (pin "2") (pinfunction "2_2") (pintype "passive"))
    )
    (net (code "59") (name "Net-(IC3-Pad9)") (class "Default")
      (node (ref "IC3") (pin "9") (pinfunction "9_9") (pintype "passive"))
      (node (ref "R27") (pin "2") (pinfunction "2_2") (pintype "passive"))
      (node (ref "R28") (pin "2") (pinfunction "2_2") (pintype "passive"))
    )
    (net (code "60") (name "Net-(IC3-Pad10)") (class "Default")
      (node (ref "IC3") (pin "10") (pinfunction "10_10") (pintype "passive"))
      (node (ref "R29") (pin "2") (pinfunction "2_2") (pintype "passive"))
      (node (ref "R30") (pin "2") (pinfunction "2_2") (pintype "passive"))
    )
    (net (code "61") (name "Net-(IC3-Pad12)") (class "Default")
      (node (ref "IC3") (pin "12") (pinfunction "12_12") (pintype "passive"))
      (node (ref "R33") (pin "2") (pinfunction "2_2") (pintype "passive"))
      (node (ref "R34") (pin "2") (pinfunction "2_2") (pintype "passive"))
    )
    (net (code "62") (name "Net-(IC3-Pad13)") (class "Default")
      (node (ref "IC3") (pin "13") (pinfunction "13_13") (pintype "passive"))
      (node (ref "R31") (pin "1") (pinfunction "1_1") (pintype "passive"))
      (node (ref "R32") (pin "2") (pinfunction "2_2") (pintype "passive"))
    )
    (net (code "63") (name "Net-(IC3-Pad14)") (class "Default")
      (node (ref "IC3") (pin "14") (pinfunction "14_14") (pintype "passive"))
      (node (ref "R31") (pin "2") (pinfunction "2_2") (pintype "passive"))
      (node (ref "R37") (pin "2") (pinfunction "2_2") (pintype "passive"))
    )
    (net (code "64") (name "Net-(PM1-Pad2)") (class "Default")
      (node (ref "PM1") (pin "2") (pinfunction "2_2") (pintype "passive"))
      (node (ref "R14") (pin "1") (pinfunction "1_1") (pintype "passive"))
    )
    (net (code "65") (name "Net-(Q1-Pad2)") (class "Default")
      (node (ref "Q1") (pin "2") (pinfunction "2_2") (pintype "passive"))
      (node (ref "Q2") (pin "1") (pinfunction "1_1") (pintype "passive"))
      (node (ref "Q4") (pin "1") (pinfunction "1_1") (pintype "passive"))
    )
    (net (code "66") (name "Net-(Q2-Pad3)") (class "Default")
      (node (ref "Q2") (pin "3") (pinfunction "3_3") (pintype "passive"))
      (node (ref "R7") (pin "2") (pinfunction "2_2") (pintype "passive"))
    )
    (net (code "67") (name "Net-(Q4-Pad2)") (class "Default")
      (node (ref "Q4") (pin "2") (pinfunction "2_2") (pintype "passive"))
      (node (ref "R51") (pin "1") (pinfunction "1_1") (pintype "passive"))
    )
    (net (code "68") (name "Net-(Q5-Pad1)") (class "Default")
      (node (ref "Q5") (pin "1") (pinfunction "1_1") (pintype "passive"))
      (node (ref "R51") (pin "2") (pinfunction "2_2") (pintype "passive"))
    )
    (net (code "69") (name "Net-(Q5-Pad2)") (class "Default")
      (node (ref "Q5") (pin "2") (pinfunction "2_2") (pintype "passive"))
      (node (ref "Q6") (pin "1") (pinfunction "1_1") (pintype "passive"))
    )
    (net (code "70") (name "Net-(Q9-Pad2)") (class "Default")
      (node (ref "Q9") (pin "2") (pinfunction "2_2") (pintype "passive"))
      (node (ref "R16") (pin "2") (pinfunction "2_2") (pintype "passive"))
    )
    (net (code "71") (name "Net-(Q10-Pad1)") (class "Default")
      (node (ref "Q10") (pin "1") (pinfunction "1_1") (pintype "passive"))
      (node (ref "R15") (pin "1") (pinfunction "1_1") (pintype "passive"))
      (node (ref "R17") (pin "2") (pinfunction "2_2") (pintype "passive"))
    )
    (net (code "72") (name "Net-(Q11-Pad1)") (class "Default")
      (node (ref "Q11") (pin "1") (pinfunction "1_1") (pintype "passive"))
      (node (ref "R43") (pin "1") (pinfunction "1_1") (pintype "passive"))
    )
    (net (code "73") (name "Net-(Q12-Pad1)") (class "Default")
      (node (ref "Q12") (pin "1") (pinfunction "1_1") (pintype "passive"))
      (node (ref "R44") (pin "1") (pinfunction "1_1") (pintype "passive"))
    )
    (net (code "74") (name "Net-(Q13-Pad1)") (class "Default")
      (node (ref "Q13") (pin "1") (pinfunction "1_1") (pintype "passive"))
      (node (ref "R45") (pin "1") (pinfunction "1_1") (pintype "passive"))
    )
    (net (code "75") (name "Net-(Q14-Pad1)") (class "Default")
      (node (ref "Q14") (pin "1") (pinfunction "1_1") (pintype "passive"))
      (node (ref "R46") (pin "1") (pinfunction "1_1") (pintype "passive"))
    )
    (net (code "76") (name "unconnected-(IC2-Pad1)") (class "Default")
      (node (ref "IC2") (pin "1") (pinfunction "1_1") (pintype "passive"))
    )
    (net (code "77") (name "unconnected-(IC2-Pad5)") (class "Default")
      (node (ref "IC2") (pin "5") (pinfunction "5_5") (pintype "passive"))
    )
    (net (code "78") (name "unconnected-(IC2-Pad8)") (class "Default")
      (node (ref "IC2") (pin "8") (pinfunction "8_8") (pintype "passive"))
    )
  )
)
